# M20050-1_GPS_Breakout_Board_2.net
KiCad netlist of a schematic drawn in EAGLE
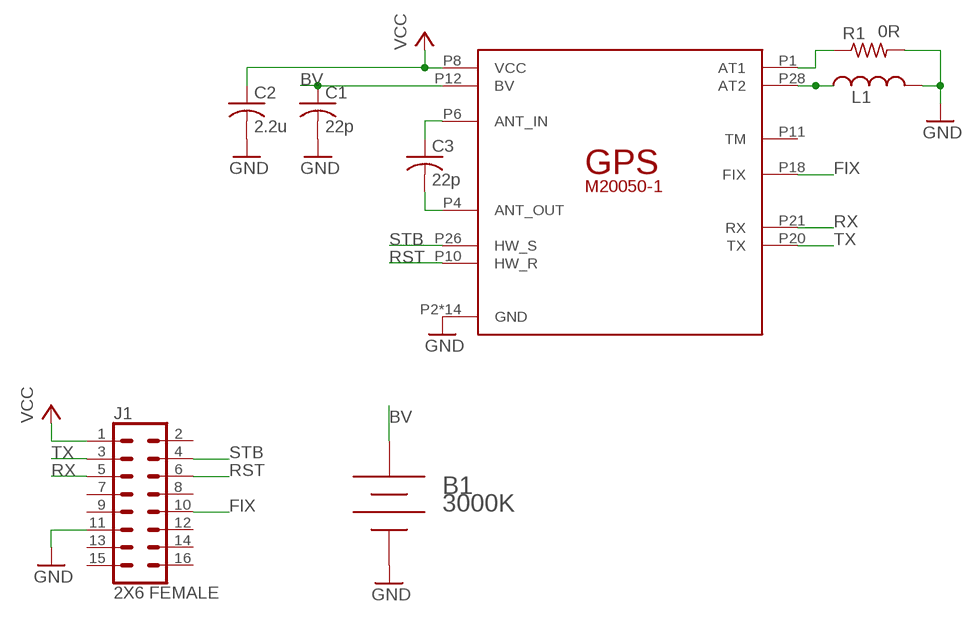
[diagram p0: schematic, sheet 1]

(export (version "E")
  (design (tool "Eeschema 10.0.6"))
  (components
    (comp (ref "A1")
      (value "GPS_M20050-1")
      (footprint "eagle-import:M20050-1_GPS")
      (libsource (lib "eagle-import") (part "GPS_M20050-1"))
    )
    (comp (ref "B1")
      (value "3000K")
      (footprint "eagle-import:3000K")
      (libsource (lib "eagle-import") (part "3000K"))
    )
    (comp (ref "C1")
      (value "22p")
      (footprint "eagle-import:C1206")
      (libsource (lib "eagle-import") (part "C-ALL_PACKAGESC1206"))
    )
    (comp (ref "C2")
      (value "2.2u")
      (footprint "eagle-import:C1206")
      (libsource (lib "eagle-import") (part "C-ALL_PACKAGESC1206"))
    )
    (comp (ref "C3")
      (value "22p")
      (footprint "eagle-import:C1206")
      (libsource (lib "eagle-import") (part "C-ALL_PACKAGESC1206"))
    )
    (comp (ref "J1")
      (value "2X6 FEMALE")
      (footprint "eagle-import:2X7")
      (libsource (lib "eagle-import") (part "SENSOR_BREAKOUTPTH_FEMALE"))
    )
    (comp (ref "L1")
      (value "1.8n")
      (footprint "eagle-import:INDC2012X105N")
      (fields
        (field (name "DIGI-KEY_PART_NUMBER") "535-11559-1-ND")
        (field (name "MF") "Abracon")
        (field (name "MP") "AIMC-0805-1N8S-T")
      )
      (libsource (lib "eagle-import") (part "AIMC-0805-1N8S-T"))
    )
    (comp (ref "R1")
      (value "0R")
      (footprint "eagle-import:R1206")
      (libsource (lib "eagle-import") (part "R-ALL_PACKAGESR1206"))
    )
  )
  (nets
    (net (code "1") (name "/BV") (class "Default")
      (node (ref "A1") (pin "P12") (pinfunction "BV_P12") (pintype "bidirectional"))
      (node (ref "B1") (pin "+") (pinfunction "+_+") (pintype "power_in"))
      (node (ref "C1") (pin "1") (pinfunction "1_1") (pintype "passive"))
    )
    (net (code "2") (name "/FIX") (class "Default")
      (node (ref "A1") (pin "P18") (pinfunction "FIX_P18") (pintype "bidirectional"))
      (node (ref "J1") (pin "10") (pinfunction "10_10") (pintype "passive"))
    )
    (net (code "3") (name "/RST") (class "Default")
      (node (ref "A1") (pin "P10") (pinfunction "HW_R_P10") (pintype "bidirectional"))
      (node (ref "J1") (pin "6") (pinfunction "6_6") (pintype "passive"))
    )
    (net (code "4") (name "/RX") (class "Default")
      (node (ref "A1") (pin "P21") (pinfunction "RX_P21") (pintype "bidirectional"))
      (node (ref "J1") (pin "5") (pinfunction "5_5") (pintype "passive"))
    )
    (net (code "5") (name "/STB") (class "Default")
      (node (ref "A1") (pin "P26") (pinfunction "HW_S_P26") (pintype "bidirectional"))
      (node (ref "J1") (pin "4") (pinfunction "4_4") (pintype "passive"))
    )
    (net (code "6") (name "/TX") (class "Default")
      (node (ref "A1") (pin "P20") (pinfunction "TX_P20") (pintype "bidirectional"))
      (node (ref "J1") (pin "3") (pinfunction "3_3") (pintype "passive"))
    )
    (net (code "7") (name "GND") (class "Default")
      (node (ref "A1") (pin "P15") (pinfunction "GND_P15") (pintype "bidirectional"))
      (node (ref "A1") (pin "P16") (pinfunction "GND_P16") (pintype "bidirectional"))
      (node (ref "A1") (pin "P17") (pinfunction "GND_P17") (pintype "bidirectional"))
      (node (ref "A1") (pin "P19") (pinfunction "GND_P19") (pintype "bidirectional"))
      (node (ref "A1") (pin "P2") (pinfunction "GND_P2") (pintype "bidirectional"))
      (node (ref "A1") (pin "P22") (pinfunction "GND_P22") (pintype "bidirectional"))
      (node (ref "A1") (pin "P23") (pinfunction "GND_P23") (pintype "bidirectional"))
      (node (ref "A1") (pin "P24") (pinfunction "GND_P24") (pintype "bidirectional"))
      (node (ref "A1") (pin "P25") (pinfunction "GND_P25") (pintype "bidirectional"))
      (node (ref "A1") (pin "P27") (pinfunction "GND_P27") (pintype "bidirectional"))
      (node (ref "A1") (pin "P3") (pinfunction "GND_P3") (pintype "bidirectional"))
      (node (ref "A1") (pin "P5") (pinfunction "GND_P5") (pintype "bidirectional"))
      (node (ref "A1") (pin "P7") (pinfunction "GND_P7") (pintype "bidirectional"))
      (node (ref "A1") (pin "P9") (pinfunction "GND_P9") (pintype "bidirectional"))
      (node (ref "B1") (pin "-") (pinfunction "-_-") (pintype "power_in"))
      (node (ref "C1") (pin "2") (pinfunction "2_2") (pintype "passive"))
      (node (ref "C2") (pin "2") (pinfunction "2_2") (pintype "passive"))
      (node (ref "J1") (pin "11") (pinfunction "11_11") (pintype "passive"))
      (node (ref "L1") (pin "2") (pinfunction "2_2") (pintype "passive"))
      (node (ref "R1") (pin "2") (pinfunction "2_2") (pintype "passive"))
    )
    (net (code "8") (name "Net-(A1-ANT_IN)") (class "Default")
      (node (ref "A1") (pin "P6") (pinfunction "ANT_IN_P6") (pintype "bidirectional"))
      (node (ref "C3") (pin "1") (pinfunction "1_1") (pintype "passive"))
    )
    (net (code "9") (name "Net-(A1-ANT_OUT)") (class "Default")
      (node (ref "A1") (pin "P4") (pinfunction "ANT_OUT_P4") (pintype "bidirectional"))
      (node (ref "C3") (pin "2") (pinfunction "2_2") (pintype "passive"))
    )
    (net (code "10") (name "Net-(A1-AT1)") (class "Default")
      (node (ref "A1") (pin "P1") (pinfunction "AT1_P1") (pintype "bidirectional"))
      (node (ref "R1") (pin "1") (pinfunction "1_1") (pintype "passive"))
    )
    (net (code "11") (name "Net-(A1-AT2)") (class "Default")
      (node (ref "A1") (pin "P28") (pinfunction "AT2_P28") (pintype "bidirectional"))
      (node (ref "L1") (pin "1") (pinfunction "1_1") (pintype "passive"))
    )
    (net (code "12") (name "VCC") (class "Default")
      (node (ref "A1") (pin "P8") (pinfunction "VCC_P8") (pintype "bidirectional"))
      (node (ref "C2") (pin "1") (pinfunction "1_1") (pintype "passive"))
      (node (ref "J1") (pin "1") (pinfunction "1_1") (pintype "passive"))
    )
    (net (code "13") (name "unconnected-(A1-TM-PadP11)") (class "Default")
      (node (ref "A1") (pin "P11") (pinfunction "TM_P11") (pintype "bidirectional"))
    )
    (net (code "14") (name "unconnected-(J1-Pad2)") (class "Default")
      (node (ref "J1") (pin "2") (pinfunction "2_2") (pintype "passive"))
    )
    (net (code "15") (name "unconnected-(J1-Pad7)") (class "Default")
      (node (ref "J1") (pin "7") (pinfunction "7_7") (pintype "passive"))
    )
    (net (code "16") (name "unconnected-(J1-Pad8)") (class "Default")
      (node (ref "J1") (pin "8") (pinfunction "8_8") (pintype "passive"))
    )
    (net (code "17") (name "unconnected-(J1-Pad9)") (class "Default")
      (node (ref "J1") (pin "9") (pinfunction "9_9") (pintype "passive"))
    )
    (net (code "18") (name "unconnected-(J1-Pad12)") (class "Default")
      (node (ref "J1") (pin "12") (pinfunction "12_12") (pintype "passive"))
    )
    (net (code "19") (name "unconnected-(J1-Pad13)") (class "Default")
      (node (ref "J1") (pin "13") (pinfunction "13_13") (pintype "passive"))
    )
    (net (code "20") (name "unconnected-(J1-Pad14)") (class "Default")
      (node (ref "J1") (pin "14") (pinfunction "14_14") (pintype "passive"))
    )
    (net (code "21") (name "unconnected-(J1-Pad15)") (class "Default")
      (node (ref "J1") (pin "15") (pinfunction "15_15") (pintype "passive"))
    )
    (net (code "22") (name "unconnected-(J1-Pad16)") (class "Default")
      (node (ref "J1") (pin "16") (pinfunction "16_16") (pintype "passive"))
    )
  )
)
